# Conn_A.net
KiCad netlist of a schematic drawn in Altium Designer
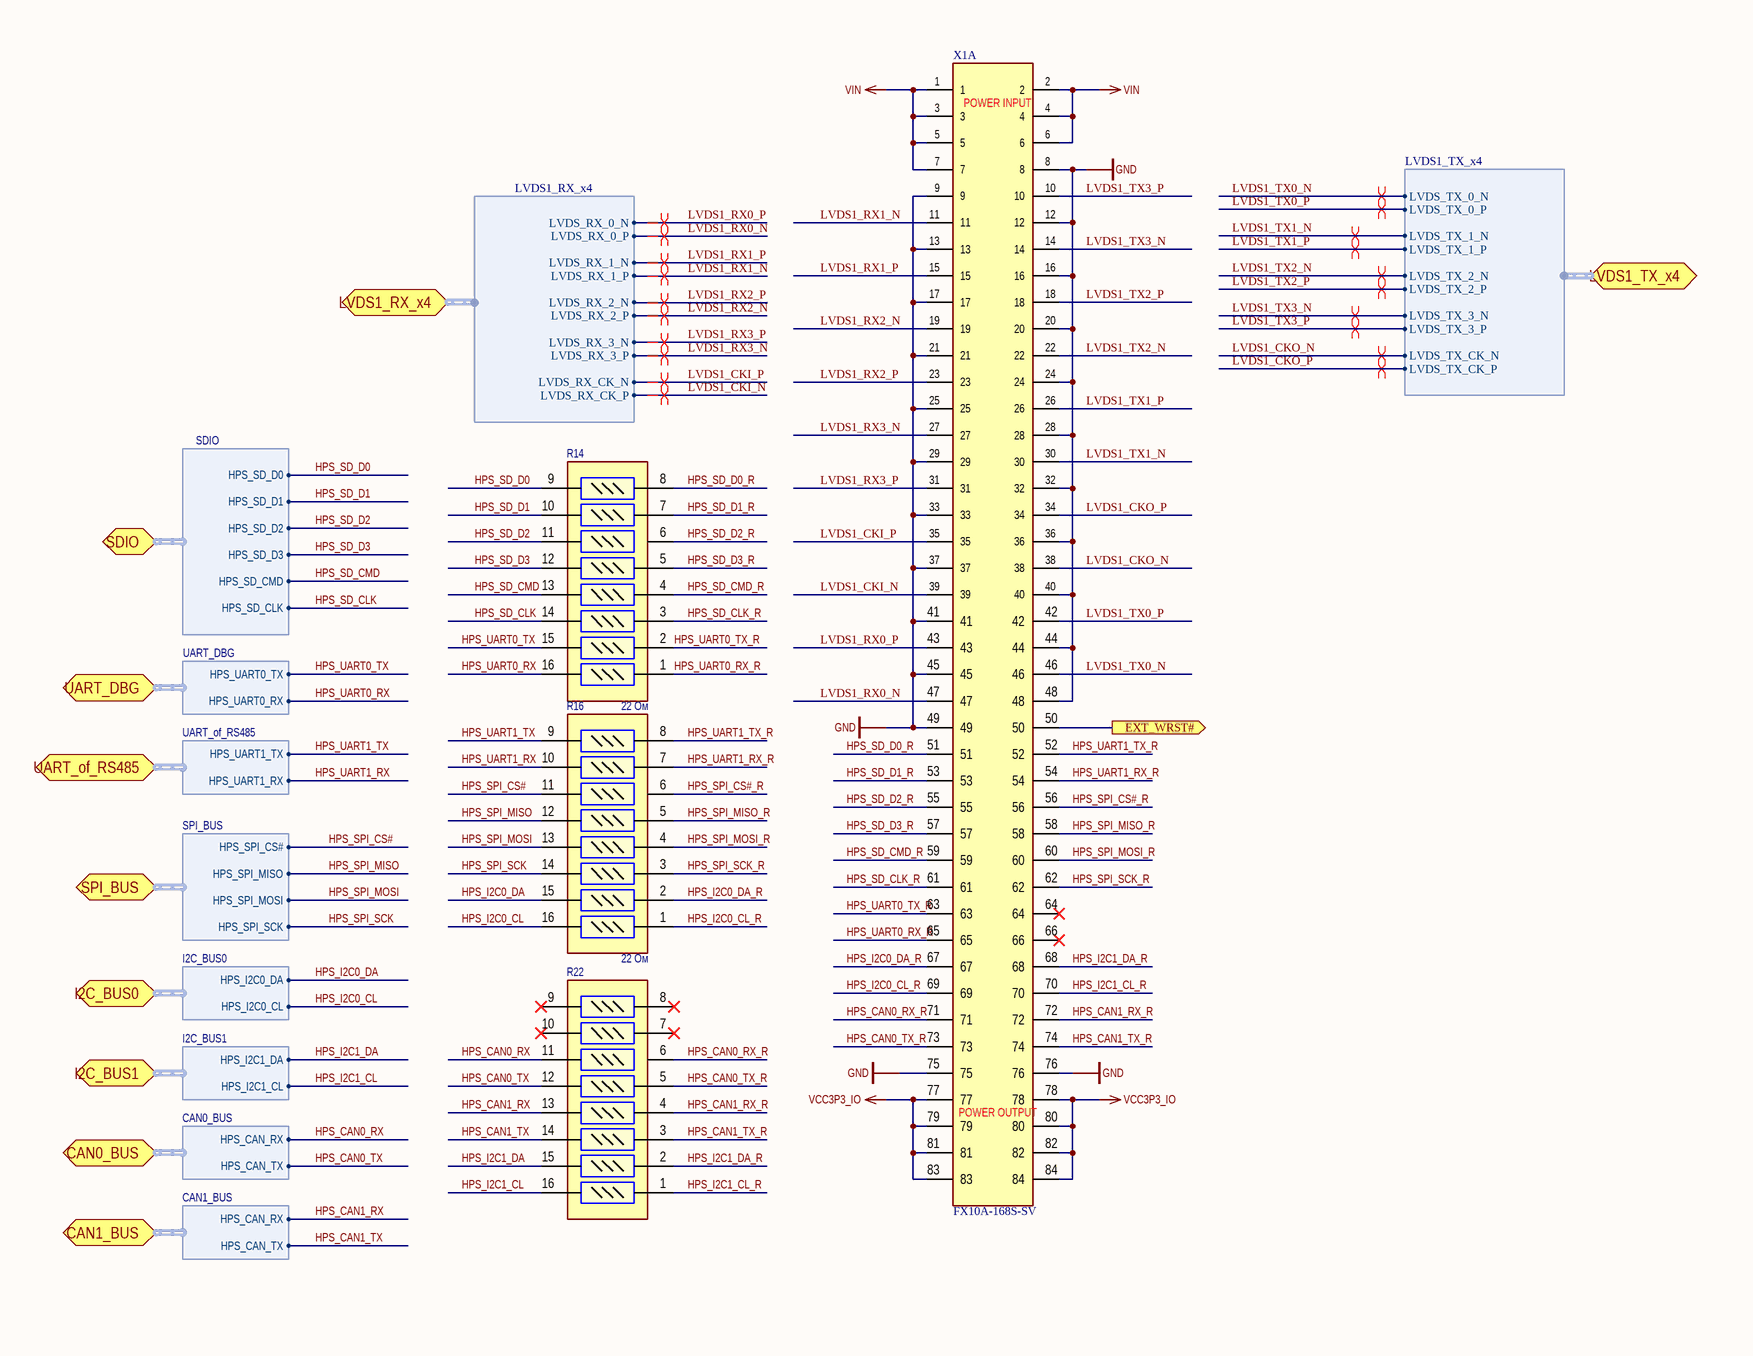
[diagram p0: Conn_A.SchDoc, left]
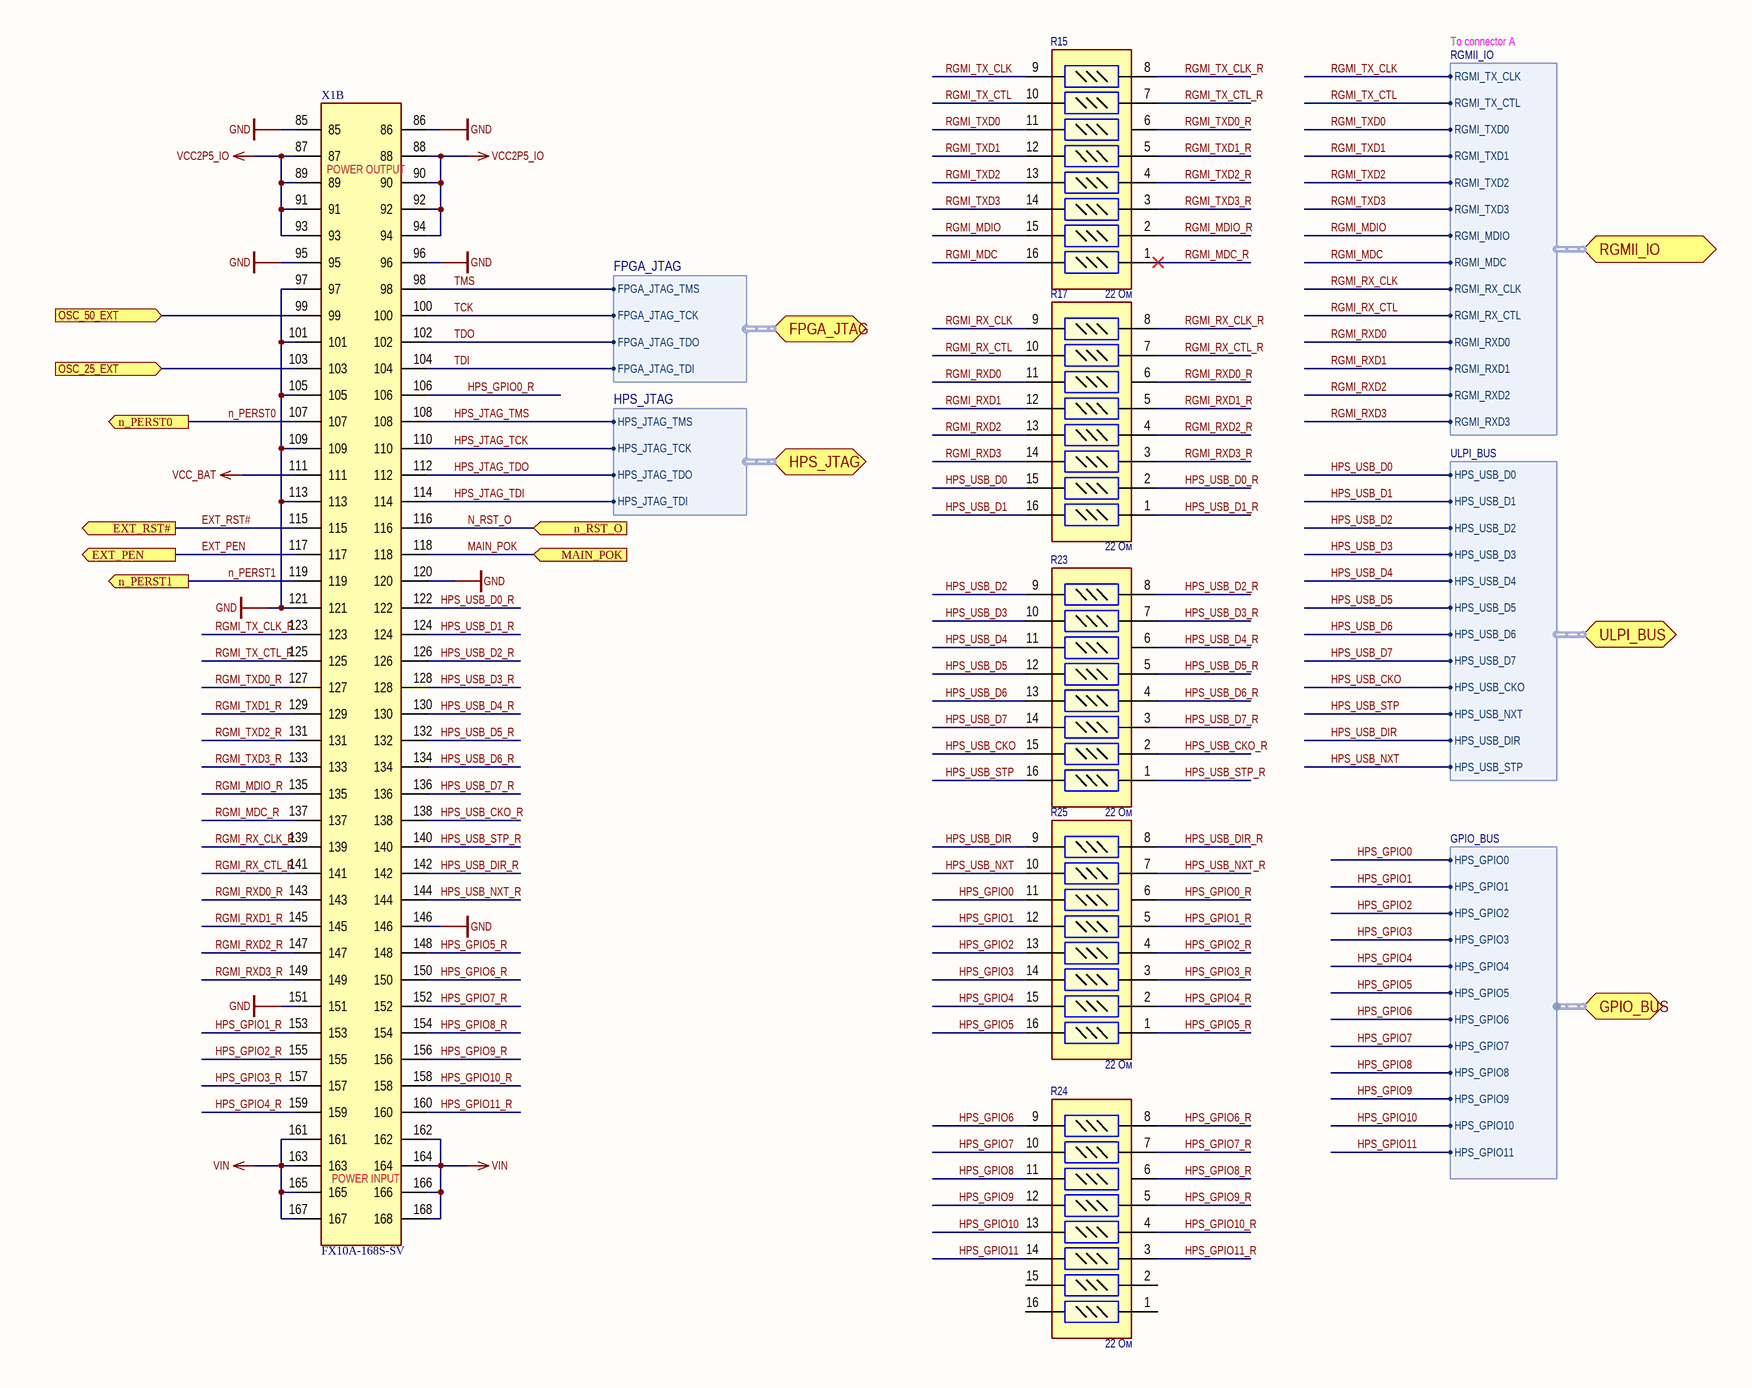
[diagram p1: Conn_A.SchDoc, right]

(export (version "E")
  (design (tool "Eeschema 10.0.6"))
  (components
    (comp (ref "R14")
      (value "22 Ом")
      (footprint "YC248")
      (description "Набор чип резисторов")
      (fields (field (name "Comment") "YC248-JR-07-22 Ом"))
      (libsource (lib "SD_IC") (part "YC248-JR-07-#"))
    )
    (comp (ref "R15")
      (value "22 Ом")
      (footprint "YC248")
      (description "Набор чип резисторов")
      (fields (field (name "Comment") "YC248-JR-07-22 Ом"))
      (libsource (lib "SD_IC") (part "YC248-JR-07-#"))
    )
    (comp (ref "R16")
      (value "22 Ом")
      (footprint "YC248")
      (description "Набор чип резисторов")
      (fields (field (name "Comment") "YC248-JR-07-22 Ом"))
      (libsource (lib "SD_IC") (part "YC248-JR-07-#"))
    )
    (comp (ref "R17")
      (value "22 Ом")
      (footprint "YC248")
      (description "Набор чип резисторов")
      (fields (field (name "Comment") "YC248-JR-07-22 Ом"))
      (libsource (lib "SD_IC") (part "YC248-JR-07-#"))
    )
    (comp (ref "R22")
      (value "YC248-JR-07-")
      (footprint "YC248")
      (description "Набор чип резисторов")
      (libsource (lib "SD_IC") (part "YC248-JR-07-#"))
    )
    (comp (ref "R23")
      (value "22 Ом")
      (footprint "YC248")
      (description "Набор чип резисторов")
      (fields (field (name "Comment") "YC248-JR-07-22 Ом"))
      (libsource (lib "SD_IC") (part "YC248-JR-07-#"))
    )
    (comp (ref "R24")
      (value "22 Ом")
      (footprint "YC248")
      (description "Набор чип резисторов")
      (fields (field (name "Comment") "YC248-JR-07-22 Ом"))
      (libsource (lib "SD_IC") (part "YC248-JR-07-#"))
    )
    (comp (ref "R25")
      (value "22 Ом")
      (footprint "YC248")
      (description "Набор чип резисторов")
      (fields (field (name "Comment") "YC248-JR-07-22 Ом"))
      (libsource (lib "SD_IC") (part "YC248-JR-07-#"))
    )
    (comp (ref "X1")
      (value "FX10A-168S-SV")
      (footprint "FX10A-168S-SV")
      (libsource (lib "SD_IC") (part "FX10A-168S-SV"))
    )
  )
  (nets
    (net (code "16") (name "/EXT_PEN") (class "Default")
      (node (ref "X1") (pin "117") (pinfunction "117_117") (pintype "passive"))
    )
    (net (code "17") (name "/EXT_RST#") (class "Default")
      (node (ref "X1") (pin "115") (pinfunction "115_115") (pintype "passive"))
    )
    (net (code "18") (name "/EXT_WRST#") (class "Default")
      (node (ref "X1") (pin "50") (pinfunction "50_50") (pintype "passive"))
    )
    (net (code "19") (name "/HPS_CAN0_RX") (class "Default")
      (node (ref "R22") (pin "11") (pintype "passive"))
    )
    (net (code "20") (name "/HPS_CAN0_RX_R") (class "Default")
      (node (ref "R22") (pin "6") (pintype "passive"))
      (node (ref "X1") (pin "71") (pinfunction "71_71") (pintype "passive"))
    )
    (net (code "21") (name "/HPS_CAN0_TX") (class "Default")
      (node (ref "R22") (pin "12") (pintype "passive"))
    )
    (net (code "22") (name "/HPS_CAN0_TX_R") (class "Default")
      (node (ref "R22") (pin "5") (pintype "passive"))
      (node (ref "X1") (pin "73") (pinfunction "73_73") (pintype "passive"))
    )
    (net (code "23") (name "/HPS_CAN1_RX") (class "Default")
      (node (ref "R22") (pin "13") (pintype "passive"))
    )
    (net (code "24") (name "/HPS_CAN1_RX_R") (class "Default")
      (node (ref "R22") (pin "4") (pintype "passive"))
      (node (ref "X1") (pin "72") (pinfunction "72_72") (pintype "passive"))
    )
    (net (code "25") (name "/HPS_CAN1_TX") (class "Default")
      (node (ref "R22") (pin "14") (pintype "passive"))
    )
    (net (code "26") (name "/HPS_CAN1_TX_R") (class "Default")
      (node (ref "R22") (pin "3") (pintype "passive"))
      (node (ref "X1") (pin "74") (pinfunction "74_74") (pintype "passive"))
    )
    (net (code "27") (name "/HPS_GPIO0") (class "Default") (node (ref "R25") (pin "11") (pintype "passive")))
    (net (code "28") (name "/HPS_GPIO0_R") (class "Default")
      (node (ref "R25") (pin "6") (pintype "passive"))
      (node (ref "X1") (pin "106") (pinfunction "106_106") (pintype "passive"))
    )
    (net (code "29") (name "/HPS_GPIO1") (class "Default") (node (ref "R25") (pin "12") (pintype "passive")))
    (net (code "30") (name "/HPS_GPIO1_R") (class "Default")
      (node (ref "R25") (pin "5") (pintype "passive"))
      (node (ref "X1") (pin "153") (pinfunction "153_153") (pintype "passive"))
    )
    (net (code "31") (name "/HPS_GPIO2") (class "Default") (node (ref "R25") (pin "13") (pintype "passive")))
    (net (code "32") (name "/HPS_GPIO2_R") (class "Default")
      (node (ref "R25") (pin "4") (pintype "passive"))
      (node (ref "X1") (pin "155") (pinfunction "155_155") (pintype "passive"))
    )
    (net (code "33") (name "/HPS_GPIO3") (class "Default") (node (ref "R25") (pin "14") (pintype "passive")))
    (net (code "34") (name "/HPS_GPIO3_R") (class "Default")
      (node (ref "R25") (pin "3") (pintype "passive"))
      (node (ref "X1") (pin "157") (pinfunction "157_157") (pintype "passive"))
    )
    (net (code "35") (name "/HPS_GPIO4") (class "Default") (node (ref "R25") (pin "15") (pintype "passive")))
    (net (code "36") (name "/HPS_GPIO4_R") (class "Default")
      (node (ref "R25") (pin "2") (pintype "passive"))
      (node (ref "X1") (pin "159") (pinfunction "159_159") (pintype "passive"))
    )
    (net (code "37") (name "/HPS_GPIO5") (class "Default") (node (ref "R25") (pin "16") (pintype "passive")))
    (net (code "38") (name "/HPS_GPIO5_R") (class "Default")
      (node (ref "R25") (pin "1") (pintype "passive"))
      (node (ref "X1") (pin "148") (pinfunction "148_148") (pintype "passive"))
    )
    (net (code "39") (name "/HPS_GPIO6") (class "Default") (node (ref "R24") (pin "9") (pintype "passive")))
    (net (code "40") (name "/HPS_GPIO6_R") (class "Default")
      (node (ref "R24") (pin "8") (pintype "passive"))
      (node (ref "X1") (pin "150") (pinfunction "150_150") (pintype "passive"))
    )
    (net (code "41") (name "/HPS_GPIO7") (class "Default") (node (ref "R24") (pin "10") (pintype "passive")))
    (net (code "42") (name "/HPS_GPIO7_R") (class "Default")
      (node (ref "R24") (pin "7") (pintype "passive"))
      (node (ref "X1") (pin "152") (pinfunction "152_152") (pintype "passive"))
    )
    (net (code "43") (name "/HPS_GPIO8") (class "Default") (node (ref "R24") (pin "11") (pintype "passive")))
    (net (code "44") (name "/HPS_GPIO8_R") (class "Default")
      (node (ref "R24") (pin "6") (pintype "passive"))
      (node (ref "X1") (pin "154") (pinfunction "154_154") (pintype "passive"))
    )
    (net (code "45") (name "/HPS_GPIO9") (class "Default") (node (ref "R24") (pin "12") (pintype "passive")))
    (net (code "46") (name "/HPS_GPIO9_R") (class "Default")
      (node (ref "R24") (pin "5") (pintype "passive"))
      (node (ref "X1") (pin "156") (pinfunction "156_156") (pintype "passive"))
    )
    (net (code "47") (name "/HPS_GPIO10") (class "Default") (node (ref "R24") (pin "13") (pintype "passive")))
    (net (code "48") (name "/HPS_GPIO10_R") (class "Default")
      (node (ref "R24") (pin "4") (pintype "passive"))
      (node (ref "X1") (pin "158") (pinfunction "158_158") (pintype "passive"))
    )
    (net (code "49") (name "/HPS_GPIO11") (class "Default") (node (ref "R24") (pin "14") (pintype "passive")))
    (net (code "50") (name "/HPS_GPIO11_R") (class "Default")
      (node (ref "R24") (pin "3") (pintype "passive"))
      (node (ref "X1") (pin "160") (pinfunction "160_160") (pintype "passive"))
    )
    (net (code "51") (name "/HPS_I2C0_CL") (class "Default")
      (node (ref "R16") (pin "16") (pintype "passive"))
    )
    (net (code "52") (name "/HPS_I2C0_CL_R") (class "Default")
      (node (ref "R16") (pin "1") (pintype "passive"))
      (node (ref "X1") (pin "69") (pinfunction "69_69") (pintype "passive"))
    )
    (net (code "53") (name "/HPS_I2C0_DA") (class "Default")
      (node (ref "R16") (pin "15") (pintype "passive"))
    )
    (net (code "54") (name "/HPS_I2C0_DA_R") (class "Default")
      (node (ref "R16") (pin "2") (pintype "passive"))
      (node (ref "X1") (pin "67") (pinfunction "67_67") (pintype "passive"))
    )
    (net (code "55") (name "/HPS_I2C1_CL") (class "Default")
      (node (ref "R22") (pin "16") (pintype "passive"))
    )
    (net (code "56") (name "/HPS_I2C1_CL_R") (class "Default")
      (node (ref "R22") (pin "1") (pintype "passive"))
      (node (ref "X1") (pin "70") (pinfunction "70_70") (pintype "passive"))
    )
    (net (code "57") (name "/HPS_I2C1_DA") (class "Default")
      (node (ref "R22") (pin "15") (pintype "passive"))
    )
    (net (code "58") (name "/HPS_I2C1_DA_R") (class "Default")
      (node (ref "R22") (pin "2") (pintype "passive"))
      (node (ref "X1") (pin "68") (pinfunction "68_68") (pintype "passive"))
    )
    (net (code "59") (name "/HPS_JTAG_TCK") (class "Default")
      (node (ref "X1") (pin "110") (pinfunction "110_110") (pintype "passive"))
    )
    (net (code "60") (name "/HPS_JTAG_TDI") (class "Default")
      (node (ref "X1") (pin "114") (pinfunction "114_114") (pintype "passive"))
    )
    (net (code "61") (name "/HPS_JTAG_TDO") (class "Default")
      (node (ref "X1") (pin "112") (pinfunction "112_112") (pintype "passive"))
    )
    (net (code "62") (name "/HPS_JTAG_TMS") (class "Default")
      (node (ref "X1") (pin "108") (pinfunction "108_108") (pintype "passive"))
    )
    (net (code "63") (name "/HPS_SD_CLK") (class "Default") (node (ref "R14") (pin "14") (pintype "passive")))
    (net (code "64") (name "/HPS_SD_CLK_R") (class "Default")
      (node (ref "R14") (pin "3") (pintype "passive"))
      (node (ref "X1") (pin "61") (pinfunction "61_61") (pintype "passive"))
    )
    (net (code "65") (name "/HPS_SD_CMD") (class "Default") (node (ref "R14") (pin "13") (pintype "passive")))
    (net (code "66") (name "/HPS_SD_CMD_R") (class "Default")
      (node (ref "R14") (pin "4") (pintype "passive"))
      (node (ref "X1") (pin "59") (pinfunction "59_59") (pintype "passive"))
    )
    (net (code "67") (name "/HPS_SD_D0") (class "Default") (node (ref "R14") (pin "9") (pintype "passive")))
    (net (code "68") (name "/HPS_SD_D0_R") (class "Default")
      (node (ref "R14") (pin "8") (pintype "passive"))
      (node (ref "X1") (pin "51") (pinfunction "51_51") (pintype "passive"))
    )
    (net (code "69") (name "/HPS_SD_D1") (class "Default") (node (ref "R14") (pin "10") (pintype "passive")))
    (net (code "70") (name "/HPS_SD_D1_R") (class "Default")
      (node (ref "R14") (pin "7") (pintype "passive"))
      (node (ref "X1") (pin "53") (pinfunction "53_53") (pintype "passive"))
    )
    (net (code "71") (name "/HPS_SD_D2") (class "Default") (node (ref "R14") (pin "11") (pintype "passive")))
    (net (code "72") (name "/HPS_SD_D2_R") (class "Default")
      (node (ref "R14") (pin "6") (pintype "passive"))
      (node (ref "X1") (pin "55") (pinfunction "55_55") (pintype "passive"))
    )
    (net (code "73") (name "/HPS_SD_D3") (class "Default") (node (ref "R14") (pin "12") (pintype "passive")))
    (net (code "74") (name "/HPS_SD_D3_R") (class "Default")
      (node (ref "R14") (pin "5") (pintype "passive"))
      (node (ref "X1") (pin "57") (pinfunction "57_57") (pintype "passive"))
    )
    (net (code "75") (name "/HPS_SPI_CS#") (class "Default")
      (node (ref "R16") (pin "11") (pintype "passive"))
    )
    (net (code "76") (name "/HPS_SPI_CS#_R") (class "Default")
      (node (ref "R16") (pin "6") (pintype "passive"))
      (node (ref "X1") (pin "56") (pinfunction "56_56") (pintype "passive"))
    )
    (net (code "77") (name "/HPS_SPI_MISO") (class "Default")
      (node (ref "R16") (pin "12") (pintype "passive"))
    )
    (net (code "78") (name "/HPS_SPI_MISO_R") (class "Default")
      (node (ref "R16") (pin "5") (pintype "passive"))
      (node (ref "X1") (pin "58") (pinfunction "58_58") (pintype "passive"))
    )
    (net (code "79") (name "/HPS_SPI_MOSI") (class "Default")
      (node (ref "R16") (pin "13") (pintype "passive"))
    )
    (net (code "80") (name "/HPS_SPI_MOSI_R") (class "Default")
      (node (ref "R16") (pin "4") (pintype "passive"))
      (node (ref "X1") (pin "60") (pinfunction "60_60") (pintype "passive"))
    )
    (net (code "81") (name "/HPS_SPI_SCK") (class "Default")
      (node (ref "R16") (pin "14") (pintype "passive"))
    )
    (net (code "82") (name "/HPS_SPI_SCK_R") (class "Default")
      (node (ref "R16") (pin "3") (pintype "passive"))
      (node (ref "X1") (pin "62") (pinfunction "62_62") (pintype "passive"))
    )
    (net (code "83") (name "/HPS_UART0_RX") (class "Default")
      (node (ref "R14") (pin "16") (pintype "passive"))
    )
    (net (code "84") (name "/HPS_UART0_RX_R") (class "Default")
      (node (ref "R14") (pin "1") (pintype "passive"))
      (node (ref "X1") (pin "65") (pinfunction "65_65") (pintype "passive"))
    )
    (net (code "85") (name "/HPS_UART0_TX") (class "Default")
      (node (ref "R14") (pin "15") (pintype "passive"))
    )
    (net (code "86") (name "/HPS_UART0_TX_R") (class "Default")
      (node (ref "R14") (pin "2") (pintype "passive"))
      (node (ref "X1") (pin "63") (pinfunction "63_63") (pintype "passive"))
    )
    (net (code "87") (name "/HPS_UART1_RX") (class "Default")
      (node (ref "R16") (pin "10") (pintype "passive"))
    )
    (net (code "88") (name "/HPS_UART1_RX_R") (class "Default")
      (node (ref "R16") (pin "7") (pintype "passive"))
      (node (ref "X1") (pin "54") (pinfunction "54_54") (pintype "passive"))
    )
    (net (code "89") (name "/HPS_UART1_TX") (class "Default")
      (node (ref "R16") (pin "9") (pintype "passive"))
    )
    (net (code "90") (name "/HPS_UART1_TX_R") (class "Default")
      (node (ref "R16") (pin "8") (pintype "passive"))
      (node (ref "X1") (pin "52") (pinfunction "52_52") (pintype "passive"))
    )
    (net (code "91") (name "/HPS_USB_CKO") (class "Default")
      (node (ref "R23") (pin "15") (pintype "passive"))
    )
    (net (code "92") (name "/HPS_USB_CKO_R") (class "Default")
      (node (ref "R23") (pin "2") (pintype "passive"))
      (node (ref "X1") (pin "138") (pinfunction "138_138") (pintype "passive"))
    )
    (net (code "93") (name "/HPS_USB_D0") (class "Default") (node (ref "R17") (pin "15") (pintype "passive")))
    (net (code "94") (name "/HPS_USB_D0_R") (class "Default")
      (node (ref "R17") (pin "2") (pintype "passive"))
      (node (ref "X1") (pin "122") (pinfunction "122_122") (pintype "passive"))
    )
    (net (code "95") (name "/HPS_USB_D1") (class "Default") (node (ref "R17") (pin "16") (pintype "passive")))
    (net (code "96") (name "/HPS_USB_D1_R") (class "Default")
      (node (ref "R17") (pin "1") (pintype "passive"))
      (node (ref "X1") (pin "124") (pinfunction "124_124") (pintype "passive"))
    )
    (net (code "97") (name "/HPS_USB_D2") (class "Default") (node (ref "R23") (pin "9") (pintype "passive")))
    (net (code "98") (name "/HPS_USB_D2_R") (class "Default")
      (node (ref "R23") (pin "8") (pintype "passive"))
      (node (ref "X1") (pin "126") (pinfunction "126_126") (pintype "passive"))
    )
    (net (code "99") (name "/HPS_USB_D3") (class "Default") (node (ref "R23") (pin "10") (pintype "passive")))
    (net (code "100") (name "/HPS_USB_D3_R") (class "Default")
      (node (ref "R23") (pin "7") (pintype "passive"))
      (node (ref "X1") (pin "128") (pinfunction "128_128") (pintype "passive"))
    )
    (net (code "101") (name "/HPS_USB_D4") (class "Default")
      (node (ref "R23") (pin "11") (pintype "passive"))
    )
    (net (code "102") (name "/HPS_USB_D4_R") (class "Default")
      (node (ref "R23") (pin "6") (pintype "passive"))
      (node (ref "X1") (pin "130") (pinfunction "130_130") (pintype "passive"))
    )
    (net (code "103") (name "/HPS_USB_D5") (class "Default")
      (node (ref "R23") (pin "12") (pintype "passive"))
    )
    (net (code "104") (name "/HPS_USB_D5_R") (class "Default")
      (node (ref "R23") (pin "5") (pintype "passive"))
      (node (ref "X1") (pin "132") (pinfunction "132_132") (pintype "passive"))
    )
    (net (code "105") (name "/HPS_USB_D6") (class "Default")
      (node (ref "R23") (pin "13") (pintype "passive"))
    )
    (net (code "106") (name "/HPS_USB_D6_R") (class "Default")
      (node (ref "R23") (pin "4") (pintype "passive"))
      (node (ref "X1") (pin "134") (pinfunction "134_134") (pintype "passive"))
    )
    (net (code "107") (name "/HPS_USB_D7") (class "Default")
      (node (ref "R23") (pin "14") (pintype "passive"))
    )
    (net (code "108") (name "/HPS_USB_D7_R") (class "Default")
      (node (ref "R23") (pin "3") (pintype "passive"))
      (node (ref "X1") (pin "136") (pinfunction "136_136") (pintype "passive"))
    )
    (net (code "109") (name "/HPS_USB_DIR") (class "Default")
      (node (ref "R25") (pin "9") (pintype "passive"))
    )
    (net (code "110") (name "/HPS_USB_DIR_R") (class "Default")
      (node (ref "R25") (pin "8") (pintype "passive"))
      (node (ref "X1") (pin "142") (pinfunction "142_142") (pintype "passive"))
    )
    (net (code "111") (name "/HPS_USB_NXT") (class "Default")
      (node (ref "R25") (pin "10") (pintype "passive"))
    )
    (net (code "112") (name "/HPS_USB_NXT_R") (class "Default")
      (node (ref "R25") (pin "7") (pintype "passive"))
      (node (ref "X1") (pin "144") (pinfunction "144_144") (pintype "passive"))
    )
    (net (code "113") (name "/HPS_USB_STP") (class "Default")
      (node (ref "R23") (pin "16") (pintype "passive"))
    )
    (net (code "114") (name "/HPS_USB_STP_R") (class "Default")
      (node (ref "R23") (pin "1") (pintype "passive"))
      (node (ref "X1") (pin "140") (pinfunction "140_140") (pintype "passive"))
    )
    (net (code "115") (name "/LVDS1_CKI_N") (class "Default")
      (node (ref "X1") (pin "39") (pinfunction "39_39") (pintype "passive"))
    )
    (net (code "116") (name "/LVDS1_CKI_P") (class "Default")
      (node (ref "X1") (pin "35") (pinfunction "35_35") (pintype "passive"))
    )
    (net (code "117") (name "/LVDS1_CKO_N") (class "Default")
      (node (ref "X1") (pin "38") (pinfunction "38_38") (pintype "passive"))
    )
    (net (code "118") (name "/LVDS1_CKO_P") (class "Default")
      (node (ref "X1") (pin "34") (pinfunction "34_34") (pintype "passive"))
    )
    (net (code "119") (name "/LVDS1_RX0_N") (class "Default")
      (node (ref "X1") (pin "47") (pinfunction "47_47") (pintype "passive"))
    )
    (net (code "120") (name "/LVDS1_RX0_P") (class "Default")
      (node (ref "X1") (pin "43") (pinfunction "43_43") (pintype "passive"))
    )
    (net (code "121") (name "/LVDS1_RX1_N") (class "Default")
      (node (ref "X1") (pin "11") (pinfunction "11_11") (pintype "passive"))
    )
    (net (code "122") (name "/LVDS1_RX1_P") (class "Default")
      (node (ref "X1") (pin "15") (pinfunction "15_15") (pintype "passive"))
    )
    (net (code "123") (name "/LVDS1_RX2_N") (class "Default")
      (node (ref "X1") (pin "19") (pinfunction "19_19") (pintype "passive"))
    )
    (net (code "124") (name "/LVDS1_RX2_P") (class "Default")
      (node (ref "X1") (pin "23") (pinfunction "23_23") (pintype "passive"))
    )
    (net (code "125") (name "/LVDS1_RX3_N") (class "Default")
      (node (ref "X1") (pin "27") (pinfunction "27_27") (pintype "passive"))
    )
    (net (code "126") (name "/LVDS1_RX3_P") (class "Default")
      (node (ref "X1") (pin "31") (pinfunction "31_31") (pintype "passive"))
    )
    (net (code "127") (name "/LVDS1_TX0_N") (class "Default")
      (node (ref "X1") (pin "46") (pinfunction "46_46") (pintype "passive"))
    )
    (net (code "128") (name "/LVDS1_TX0_P") (class "Default")
      (node (ref "X1") (pin "42") (pinfunction "42_42") (pintype "passive"))
    )
    (net (code "129") (name "/LVDS1_TX1_N") (class "Default")
      (node (ref "X1") (pin "30") (pinfunction "30_30") (pintype "passive"))
    )
    (net (code "130") (name "/LVDS1_TX1_P") (class "Default")
      (node (ref "X1") (pin "26") (pinfunction "26_26") (pintype "passive"))
    )
    (net (code "131") (name "/LVDS1_TX2_N") (class "Default")
      (node (ref "X1") (pin "22") (pinfunction "22_22") (pintype "passive"))
    )
    (net (code "132") (name "/LVDS1_TX2_P") (class "Default")
      (node (ref "X1") (pin "18") (pinfunction "18_18") (pintype "passive"))
    )
    (net (code "133") (name "/LVDS1_TX3_N") (class "Default")
      (node (ref "X1") (pin "14") (pinfunction "14_14") (pintype "passive"))
    )
    (net (code "134") (name "/LVDS1_TX3_P") (class "Default")
      (node (ref "X1") (pin "10") (pinfunction "10_10") (pintype "passive"))
    )
    (net (code "135") (name "/MAIN_POK") (class "Default")
      (node (ref "X1") (pin "118") (pinfunction "118_118") (pintype "passive"))
    )
    (net (code "136") (name "/N_RST_O") (class "Default")
      (node (ref "X1") (pin "116") (pinfunction "116_116") (pintype "passive"))
    )
    (net (code "137") (name "/OSC_25_EXT") (class "Default")
      (node (ref "X1") (pin "103") (pinfunction "103_103") (pintype "passive"))
    )
    (net (code "138") (name "/OSC_50_EXT") (class "Default")
      (node (ref "X1") (pin "99") (pinfunction "99_99") (pintype "passive"))
    )
    (net (code "139") (name "/RGMI_MDC") (class "Default") (node (ref "R15") (pin "16") (pintype "passive")))
    (net (code "140") (name "/RGMI_MDC_R") (class "Default")
      (node (ref "R15") (pin "1") (pintype "passive"))
      (node (ref "X1") (pin "137") (pinfunction "137_137") (pintype "passive"))
    )
    (net (code "141") (name "/RGMI_MDIO") (class "Default") (node (ref "R15") (pin "15") (pintype "passive")))
    (net (code "142") (name "/RGMI_MDIO_R") (class "Default")
      (node (ref "R15") (pin "2") (pintype "passive"))
      (node (ref "X1") (pin "135") (pinfunction "135_135") (pintype "passive"))
    )
    (net (code "143") (name "/RGMI_RXD0") (class "Default") (node (ref "R17") (pin "11") (pintype "passive")))
    (net (code "144") (name "/RGMI_RXD0_R") (class "Default")
      (node (ref "R17") (pin "6") (pintype "passive"))
      (node (ref "X1") (pin "143") (pinfunction "143_143") (pintype "passive"))
    )
    (net (code "145") (name "/RGMI_RXD1") (class "Default") (node (ref "R17") (pin "12") (pintype "passive")))
    (net (code "146") (name "/RGMI_RXD1_R") (class "Default")
      (node (ref "R17") (pin "5") (pintype "passive"))
      (node (ref "X1") (pin "145") (pinfunction "145_145") (pintype "passive"))
    )
    (net (code "147") (name "/RGMI_RXD2") (class "Default") (node (ref "R17") (pin "13") (pintype "passive")))
    (net (code "148") (name "/RGMI_RXD2_R") (class "Default")
      (node (ref "R17") (pin "4") (pintype "passive"))
      (node (ref "X1") (pin "147") (pinfunction "147_147") (pintype "passive"))
    )
    (net (code "149") (name "/RGMI_RXD3") (class "Default") (node (ref "R17") (pin "14") (pintype "passive")))
    (net (code "150") (name "/RGMI_RXD3_R") (class "Default")
      (node (ref "R17") (pin "3") (pintype "passive"))
      (node (ref "X1") (pin "149") (pinfunction "149_149") (pintype "passive"))
    )
    (net (code "151") (name "/RGMI_RX_CLK") (class "Default")
      (node (ref "R17") (pin "9") (pintype "passive"))
    )
    (net (code "152") (name "/RGMI_RX_CLK_R") (class "Default")
      (node (ref "R17") (pin "8") (pintype "passive"))
      (node (ref "X1") (pin "139") (pinfunction "139_139") (pintype "passive"))
    )
    (net (code "153") (name "/RGMI_RX_CTL") (class "Default")
      (node (ref "R17") (pin "10") (pintype "passive"))
    )
    (net (code "154") (name "/RGMI_RX_CTL_R") (class "Default")
      (node (ref "R17") (pin "7") (pintype "passive"))
      (node (ref "X1") (pin "141") (pinfunction "141_141") (pintype "passive"))
    )
    (net (code "155") (name "/RGMI_TXD0") (class "Default") (node (ref "R15") (pin "11") (pintype "passive")))
    (net (code "156") (name "/RGMI_TXD0_R") (class "Default")
      (node (ref "R15") (pin "6") (pintype "passive"))
      (node (ref "X1") (pin "127") (pinfunction "127_127") (pintype "passive"))
    )
    (net (code "157") (name "/RGMI_TXD1") (class "Default") (node (ref "R15") (pin "12") (pintype "passive")))
    (net (code "158") (name "/RGMI_TXD1_R") (class "Default")
      (node (ref "R15") (pin "5") (pintype "passive"))
      (node (ref "X1") (pin "129") (pinfunction "129_129") (pintype "passive"))
    )
    (net (code "159") (name "/RGMI_TXD2") (class "Default") (node (ref "R15") (pin "13") (pintype "passive")))
    (net (code "160") (name "/RGMI_TXD2_R") (class "Default")
      (node (ref "R15") (pin "4") (pintype "passive"))
      (node (ref "X1") (pin "131") (pinfunction "131_131") (pintype "passive"))
    )
    (net (code "161") (name "/RGMI_TXD3") (class "Default") (node (ref "R15") (pin "14") (pintype "passive")))
    (net (code "162") (name "/RGMI_TXD3_R") (class "Default")
      (node (ref "R15") (pin "3") (pintype "passive"))
      (node (ref "X1") (pin "133") (pinfunction "133_133") (pintype "passive"))
    )
    (net (code "163") (name "/RGMI_TX_CLK") (class "Default")
      (node (ref "R15") (pin "9") (pintype "passive"))
    )
    (net (code "164") (name "/RGMI_TX_CLK_R") (class "Default")
      (node (ref "R15") (pin "8") (pintype "passive"))
      (node (ref "X1") (pin "123") (pinfunction "123_123") (pintype "passive"))
    )
    (net (code "165") (name "/RGMI_TX_CTL") (class "Default")
      (node (ref "R15") (pin "10") (pintype "passive"))
    )
    (net (code "166") (name "/RGMI_TX_CTL_R") (class "Default")
      (node (ref "R15") (pin "7") (pintype "passive"))
      (node (ref "X1") (pin "125") (pinfunction "125_125") (pintype "passive"))
    )
    (net (code "167") (name "/TCK") (class "Default")
      (node (ref "X1") (pin "100") (pinfunction "100_100") (pintype "passive"))
    )
    (net (code "168") (name "/TDI") (class "Default")
      (node (ref "X1") (pin "104") (pinfunction "104_104") (pintype "passive"))
    )
    (net (code "169") (name "/TDO") (class "Default")
      (node (ref "X1") (pin "102") (pinfunction "102_102") (pintype "passive"))
    )
    (net (code "170") (name "/TMS") (class "Default")
      (node (ref "X1") (pin "98") (pinfunction "98_98") (pintype "passive"))
    )
    (net (code "171") (name "/n_PERST0") (class "Default")
      (node (ref "X1") (pin "107") (pinfunction "107_107") (pintype "passive"))
    )
    (net (code "172") (name "/n_PERST1") (class "Default")
      (node (ref "X1") (pin "119") (pinfunction "119_119") (pintype "passive"))
    )
    (net (code "188") (name "GND") (class "Default")
      (node (ref "X1") (pin "101") (pinfunction "101_101") (pintype "passive"))
      (node (ref "X1") (pin "105") (pinfunction "105_105") (pintype "passive"))
      (node (ref "X1") (pin "109") (pinfunction "109_109") (pintype "passive"))
      (node (ref "X1") (pin "113") (pinfunction "113_113") (pintype "passive"))
      (node (ref "X1") (pin "12") (pinfunction "12_12") (pintype "passive"))
      (node (ref "X1") (pin "120") (pinfunction "120_120") (pintype "passive"))
      (node (ref "X1") (pin "121") (pinfunction "121_121") (pintype "passive"))
      (node (ref "X1") (pin "13") (pinfunction "13_13") (pintype "passive"))
      (node (ref "X1") (pin "146") (pinfunction "146_146") (pintype "passive"))
      (node (ref "X1") (pin "151") (pinfunction "151_151") (pintype "passive"))
      (node (ref "X1") (pin "16") (pinfunction "16_16") (pintype "passive"))
      (node (ref "X1") (pin "17") (pinfunction "17_17") (pintype "passive"))
      (node (ref "X1") (pin "20") (pinfunction "20_20") (pintype "passive"))
      (node (ref "X1") (pin "21") (pinfunction "21_21") (pintype "passive"))
      (node (ref "X1") (pin "24") (pinfunction "24_24") (pintype "passive"))
      (node (ref "X1") (pin "25") (pinfunction "25_25") (pintype "passive"))
      (node (ref "X1") (pin "28") (pinfunction "28_28") (pintype "passive"))
      (node (ref "X1") (pin "29") (pinfunction "29_29") (pintype "passive"))
      (node (ref "X1") (pin "32") (pinfunction "32_32") (pintype "passive"))
      (node (ref "X1") (pin "33") (pinfunction "33_33") (pintype "passive"))
      (node (ref "X1") (pin "36") (pinfunction "36_36") (pintype "passive"))
      (node (ref "X1") (pin "37") (pinfunction "37_37") (pintype "passive"))
      (node (ref "X1") (pin "40") (pinfunction "40_40") (pintype "passive"))
      (node (ref "X1") (pin "41") (pinfunction "41_41") (pintype "passive"))
      (node (ref "X1") (pin "44") (pinfunction "44_44") (pintype "passive"))
      (node (ref "X1") (pin "45") (pinfunction "45_45") (pintype "passive"))
      (node (ref "X1") (pin "48") (pinfunction "48_48") (pintype "passive"))
      (node (ref "X1") (pin "49") (pinfunction "49_49") (pintype "passive"))
      (node (ref "X1") (pin "75") (pinfunction "75_75") (pintype "passive"))
      (node (ref "X1") (pin "76") (pinfunction "76_76") (pintype "passive"))
      (node (ref "X1") (pin "8") (pinfunction "8_8") (pintype "passive"))
      (node (ref "X1") (pin "85") (pinfunction "85_85") (pintype "passive"))
      (node (ref "X1") (pin "86") (pinfunction "86_86") (pintype "passive"))
      (node (ref "X1") (pin "9") (pinfunction "9_9") (pintype "passive"))
      (node (ref "X1") (pin "95") (pinfunction "95_95") (pintype "passive"))
      (node (ref "X1") (pin "96") (pinfunction "96_96") (pintype "passive"))
      (node (ref "X1") (pin "97") (pinfunction "97_97") (pintype "passive"))
    )
    (net (code "189") (name "VCC2P5_IO") (class "Default")
      (node (ref "X1") (pin "87") (pinfunction "87_87") (pintype "passive"))
      (node (ref "X1") (pin "88") (pinfunction "88_88") (pintype "passive"))
      (node (ref "X1") (pin "89") (pinfunction "89_89") (pintype "passive"))
      (node (ref "X1") (pin "90") (pinfunction "90_90") (pintype "passive"))
      (node (ref "X1") (pin "91") (pinfunction "91_91") (pintype "passive"))
      (node (ref "X1") (pin "92") (pinfunction "92_92") (pintype "passive"))
      (node (ref "X1") (pin "93") (pinfunction "93_93") (pintype "passive"))
      (node (ref "X1") (pin "94") (pinfunction "94_94") (pintype "passive"))
    )
    (net (code "190") (name "VCC3P3_IO") (class "Default")
      (node (ref "X1") (pin "77") (pinfunction "77_77") (pintype "passive"))
      (node (ref "X1") (pin "78") (pinfunction "78_78") (pintype "passive"))
      (node (ref "X1") (pin "79") (pinfunction "79_79") (pintype "passive"))
      (node (ref "X1") (pin "80") (pinfunction "80_80") (pintype "passive"))
      (node (ref "X1") (pin "81") (pinfunction "81_81") (pintype "passive"))
      (node (ref "X1") (pin "82") (pinfunction "82_82") (pintype "passive"))
      (node (ref "X1") (pin "83") (pinfunction "83_83") (pintype "passive"))
      (node (ref "X1") (pin "84") (pinfunction "84_84") (pintype "passive"))
    )
    (net (code "191") (name "VCC_BAT") (class "Default")
      (node (ref "X1") (pin "111") (pinfunction "111_111") (pintype "passive"))
    )
    (net (code "192") (name "VIN") (class "Default")
      (node (ref "X1") (pin "1") (pinfunction "1_1") (pintype "passive"))
      (node (ref "X1") (pin "161") (pinfunction "161_161") (pintype "passive"))
      (node (ref "X1") (pin "162") (pinfunction "162_162") (pintype "passive"))
      (node (ref "X1") (pin "163") (pinfunction "163_163") (pintype "passive"))
      (node (ref "X1") (pin "164") (pinfunction "164_164") (pintype "passive"))
      (node (ref "X1") (pin "165") (pinfunction "165_165") (pintype "passive"))
      (node (ref "X1") (pin "166") (pinfunction "166_166") (pintype "passive"))
      (node (ref "X1") (pin "167") (pinfunction "167_167") (pintype "passive"))
      (node (ref "X1") (pin "168") (pinfunction "168_168") (pintype "passive"))
      (node (ref "X1") (pin "2") (pinfunction "2_2") (pintype "passive"))
      (node (ref "X1") (pin "3") (pinfunction "3_3") (pintype "passive"))
      (node (ref "X1") (pin "4") (pinfunction "4_4") (pintype "passive"))
      (node (ref "X1") (pin "5") (pinfunction "5_5") (pintype "passive"))
      (node (ref "X1") (pin "6") (pinfunction "6_6") (pintype "passive"))
      (node (ref "X1") (pin "7") (pinfunction "7_7") (pintype "passive"))
    )
    (net (code "193") (name "unconnected-(R22-Pad7)") (class "Default")
      (node (ref "R22") (pin "7") (pintype "passive+no_connect"))
    )
    (net (code "194") (name "unconnected-(R22-Pad8)") (class "Default")
      (node (ref "R22") (pin "8") (pintype "passive+no_connect"))
    )
    (net (code "195") (name "unconnected-(R22-Pad9)") (class "Default")
      (node (ref "R22") (pin "9") (pintype "passive+no_connect"))
    )
    (net (code "196") (name "unconnected-(R22-Pad10)") (class "Default")
      (node (ref "R22") (pin "10") (pintype "passive+no_connect"))
    )
    (net (code "197") (name "unconnected-(R24-Pad1)") (class "Default")
      (node (ref "R24") (pin "1") (pintype "passive"))
    )
    (net (code "198") (name "unconnected-(R24-Pad2)") (class "Default")
      (node (ref "R24") (pin "2") (pintype "passive"))
    )
    (net (code "199") (name "unconnected-(R24-Pad15)") (class "Default")
      (node (ref "R24") (pin "15") (pintype "passive"))
    )
    (net (code "200") (name "unconnected-(R24-Pad16)") (class "Default")
      (node (ref "R24") (pin "16") (pintype "passive"))
    )
    (net (code "201") (name "unconnected-(X1-Pad64)") (class "Default")
      (node (ref "X1") (pin "64") (pinfunction "64_64") (pintype "passive+no_connect"))
    )
    (net (code "202") (name "unconnected-(X1-Pad66)") (class "Default")
      (node (ref "X1") (pin "66") (pinfunction "66_66") (pintype "passive+no_connect"))
    )
  )
)
